# nrf24l01_r1.net
KiCad netlist of a schematic drawn in EAGLE
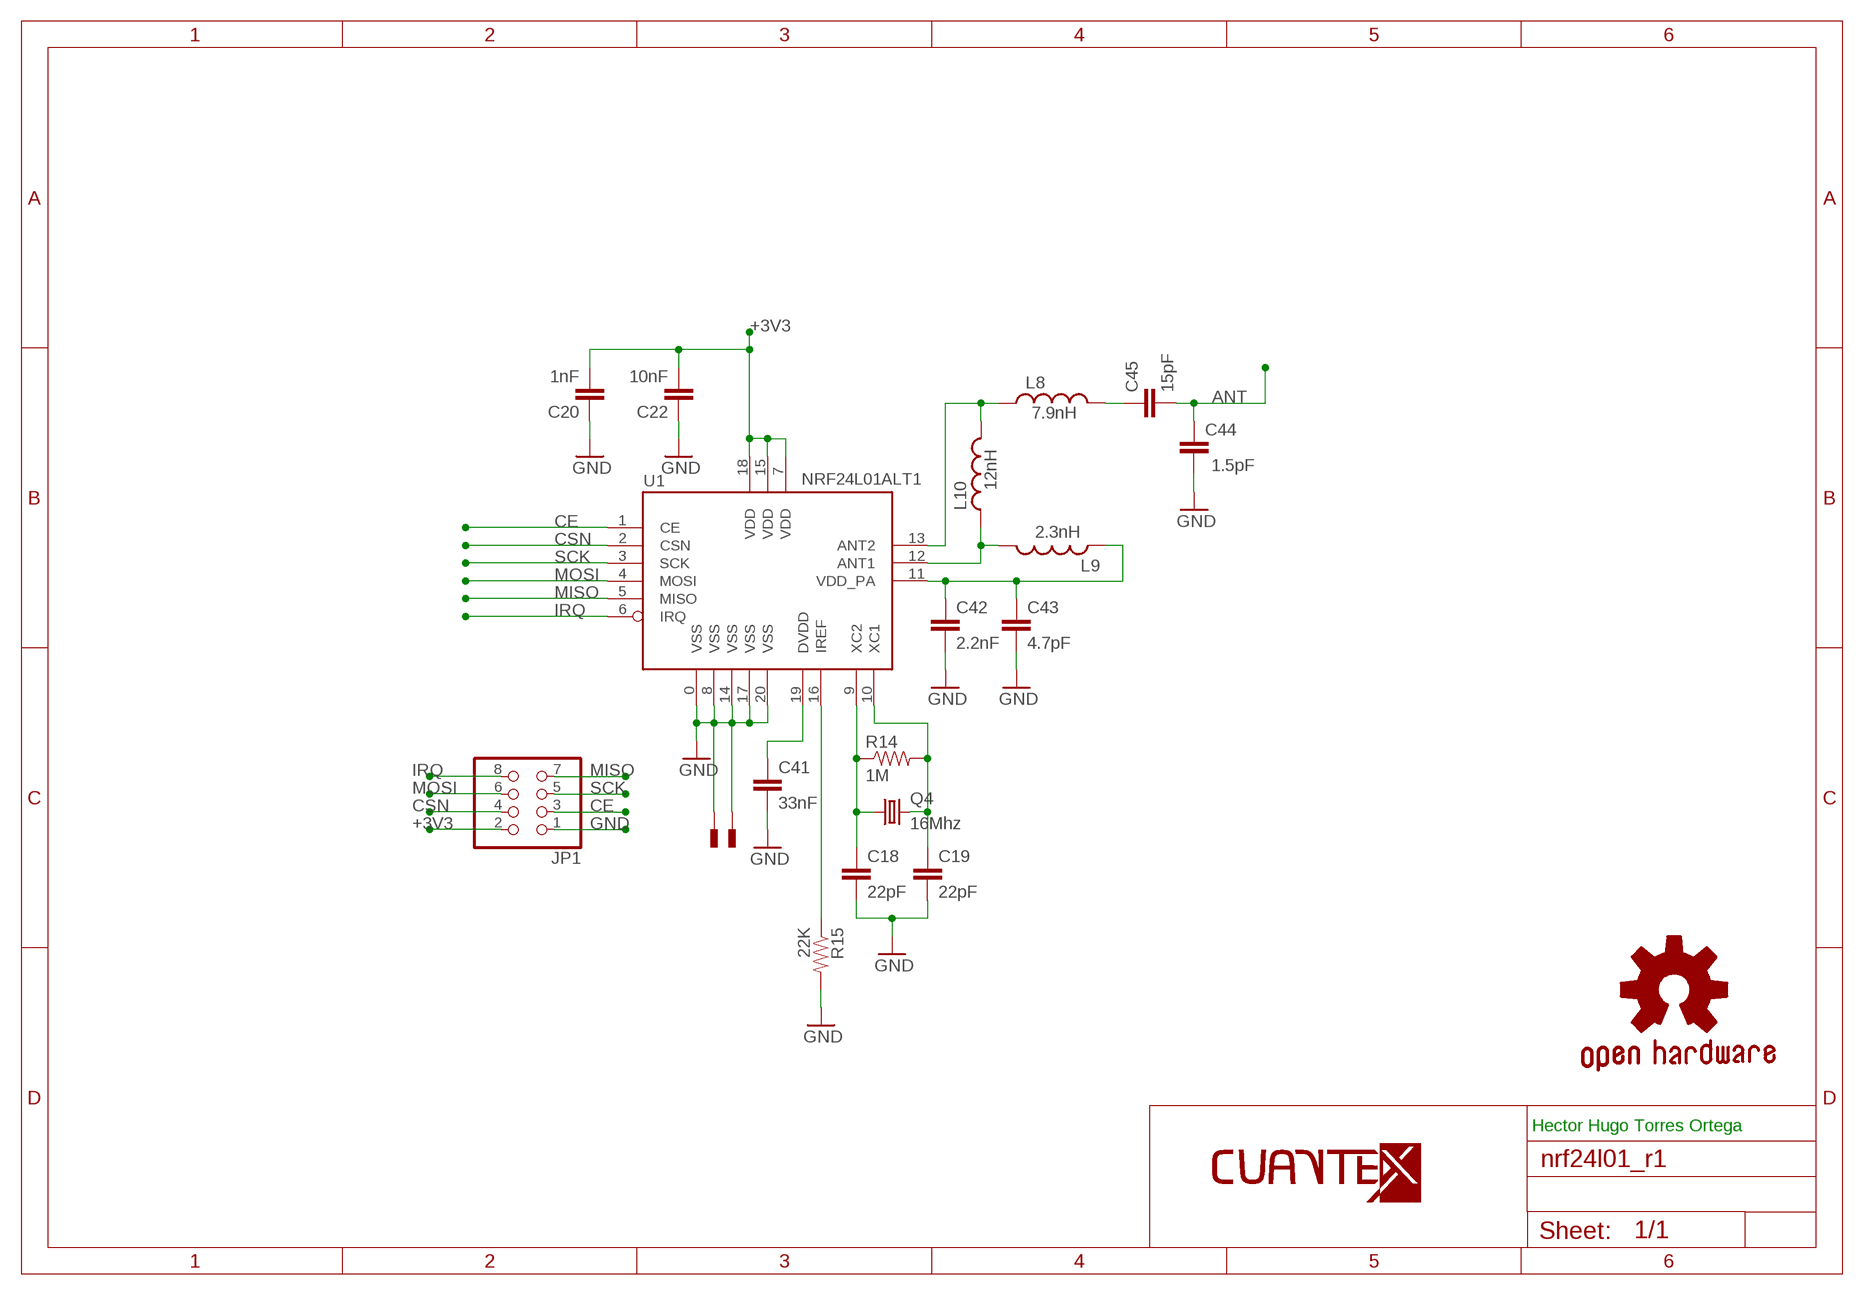
[diagram p0: schematic, sheet 1]

(export (version "E")
  (design (tool "Eeschema 10.0.6"))
  (components
    (comp (ref "C18")
      (value "22pF")
      (footprint "eagle-import:0402-CAP")
      (libsource (lib "eagle-import") (part "CAP0402-CAP"))
    )
    (comp (ref "C19")
      (value "22pF")
      (footprint "eagle-import:0402-CAP")
      (libsource (lib "eagle-import") (part "CAP0402-CAP"))
    )
    (comp (ref "C20")
      (value "1nF")
      (footprint "eagle-import:0402-CAP")
      (libsource (lib "eagle-import") (part "CAP0402-CAP"))
    )
    (comp (ref "C22")
      (value "10nF")
      (footprint "eagle-import:0402-CAP")
      (libsource (lib "eagle-import") (part "CAP0402-CAP"))
    )
    (comp (ref "C41")
      (value "33nF")
      (footprint "eagle-import:0402-CAP")
      (libsource (lib "eagle-import") (part "CAP0402-CAP"))
    )
    (comp (ref "C42")
      (value "2.2nF")
      (footprint "eagle-import:0402-CAP")
      (libsource (lib "eagle-import") (part "CAP0402-CAP"))
    )
    (comp (ref "C43")
      (value "4.7pF")
      (footprint "eagle-import:0402-CAP")
      (libsource (lib "eagle-import") (part "CAP0402-CAP"))
    )
    (comp (ref "C44")
      (value "1.5pF")
      (footprint "eagle-import:0402-CAP")
      (libsource (lib "eagle-import") (part "CAP0402-CAP"))
    )
    (comp (ref "C45")
      (value "15pF")
      (footprint "eagle-import:0402-CAP")
      (libsource (lib "eagle-import") (part "CAP0402-CAP"))
    )
    (comp (ref "GOLD_ORB_SM1")
      (value "OSHWLOGO_GOLD_ORB_SM")
      (footprint "eagle-import:OSHW2")
      (libsource (lib "eagle-import") (part "OSHWLOGO_GOLD_ORB_SM"))
    )
    (comp (ref "JP1")
      (value "PINHD-2X4")
      (footprint "eagle-import:2X04")
      (libsource (lib "eagle-import") (part "PINHD-2X4"))
    )
    (comp (ref "L8")
      (value "7.9nH")
      (footprint "eagle-import:C0402")
      (libsource (lib "eagle-import") (part "INDUCTOR0402"))
    )
    (comp (ref "L9")
      (value "2.3nH")
      (footprint "eagle-import:C0402")
      (libsource (lib "eagle-import") (part "INDUCTOR0402"))
    )
    (comp (ref "L10")
      (value "12nH")
      (footprint "eagle-import:C0402")
      (libsource (lib "eagle-import") (part "INDUCTOR0402"))
    )
    (comp (ref "Q4")
      (value "16Mhz")
      (footprint "eagle-import:HC49_S")
      (libsource (lib "eagle-import") (part "CRYSTALHC49S"))
    )
    (comp (ref "R14")
      (value "1M")
      (footprint "eagle-import:0402-RES")
      (libsource (lib "eagle-import") (part "RESISTOR0402-RES"))
    )
    (comp (ref "R15")
      (value "22K")
      (footprint "eagle-import:0402-RES")
      (libsource (lib "eagle-import") (part "RESISTOR0402-RES"))
    )
    (comp (ref "U$1")
      (value "LOGO-BOT-20MM")
      (footprint "eagle-import:B-20")
      (libsource (lib "eagle-import") (part "LOGO-BOT-20MM"))
    )
    (comp (ref "U$9")
      (value "PAD")
      (footprint "eagle-import:PAD-0.008")
      (libsource (lib "eagle-import") (part "PAD"))
    )
    (comp (ref "U$10")
      (value "PAD")
      (footprint "eagle-import:PAD-0.008")
      (libsource (lib "eagle-import") (part "PAD"))
    )
    (comp (ref "U1")
      (value "NRF24L01ALT1")
      (footprint "eagle-import:QFN20_ALT1")
      (libsource (lib "eagle-import") (part "NRF24L01ALT1"))
    )
  )
  (nets
    (net (code "1") (name "/+3V3") (class "Default")
      (node (ref "C20") (pin "2") (pinfunction "2_2") (pintype "passive"))
      (node (ref "C22") (pin "2") (pinfunction "2_2") (pintype "passive"))
      (node (ref "JP1") (pin "2") (pinfunction "2_2") (pintype "passive"))
      (node (ref "U1") (pin "15") (pinfunction "VDD_15") (pintype "power_in"))
      (node (ref "U1") (pin "18") (pinfunction "VDD_18") (pintype "power_in"))
      (node (ref "U1") (pin "7") (pinfunction "VDD_7") (pintype "power_in"))
    )
    (net (code "2") (name "/ANT") (class "Default")
      (node (ref "C44") (pin "2") (pinfunction "2_2") (pintype "passive"))
      (node (ref "C45") (pin "2") (pinfunction "2_2") (pintype "passive"))
    )
    (net (code "3") (name "/CE") (class "Default")
      (node (ref "JP1") (pin "3") (pinfunction "3_3") (pintype "passive"))
      (node (ref "U1") (pin "1") (pinfunction "CE_1") (pintype "input"))
    )
    (net (code "4") (name "/CSN") (class "Default")
      (node (ref "JP1") (pin "4") (pinfunction "4_4") (pintype "passive"))
      (node (ref "U1") (pin "2") (pinfunction "CSN_2") (pintype "input"))
    )
    (net (code "5") (name "/IRQ") (class "Default")
      (node (ref "JP1") (pin "8") (pinfunction "8_8") (pintype "passive"))
      (node (ref "U1") (pin "6") (pinfunction "IRQ_6") (pintype "output"))
    )
    (net (code "6") (name "/MISO") (class "Default")
      (node (ref "JP1") (pin "7") (pinfunction "7_7") (pintype "passive"))
      (node (ref "U1") (pin "5") (pinfunction "MISO_5") (pintype "output"))
    )
    (net (code "7") (name "/MOSI") (class "Default")
      (node (ref "JP1") (pin "6") (pinfunction "6_6") (pintype "passive"))
      (node (ref "U1") (pin "4") (pinfunction "MOSI_4") (pintype "input"))
    )
    (net (code "8") (name "/SCK") (class "Default")
      (node (ref "JP1") (pin "5") (pinfunction "5_5") (pintype "passive"))
      (node (ref "U1") (pin "3") (pinfunction "SCK_3") (pintype "input"))
    )
    (net (code "9") (name "GND") (class "Default")
      (node (ref "C18") (pin "2") (pinfunction "2_2") (pintype "passive"))
      (node (ref "C19") (pin "2") (pinfunction "2_2") (pintype "passive"))
      (node (ref "C20") (pin "1") (pinfunction "1_1") (pintype "passive"))
      (node (ref "C22") (pin "1") (pinfunction "1_1") (pintype "passive"))
      (node (ref "C41") (pin "2") (pinfunction "2_2") (pintype "passive"))
      (node (ref "C42") (pin "2") (pinfunction "2_2") (pintype "passive"))
      (node (ref "C43") (pin "2") (pinfunction "2_2") (pintype "passive"))
      (node (ref "C44") (pin "1") (pinfunction "1_1") (pintype "passive"))
      (node (ref "JP1") (pin "1") (pinfunction "1_1") (pintype "passive"))
      (node (ref "R15") (pin "2") (pinfunction "2_2") (pintype "passive"))
      (node (ref "U$10") (pin "P$1") (pinfunction "P$1_P$1") (pintype "bidirectional"))
      (node (ref "U$9") (pin "P$1") (pinfunction "P$1_P$1") (pintype "bidirectional"))
      (node (ref "U1") (pin "0") (pinfunction "VSS_0") (pintype "power_in"))
      (node (ref "U1") (pin "14") (pinfunction "VSS_14") (pintype "power_in"))
      (node (ref "U1") (pin "17") (pinfunction "VSS_17") (pintype "power_in"))
      (node (ref "U1") (pin "20") (pinfunction "VSS_20") (pintype "power_in"))
      (node (ref "U1") (pin "8") (pinfunction "VSS_8") (pintype "power_in"))
    )
    (net (code "10") (name "Net-(C45-Pad1)") (class "Default")
      (node (ref "C45") (pin "1") (pinfunction "1_1") (pintype "passive"))
      (node (ref "L8") (pin "2") (pinfunction "2_2") (pintype "passive"))
    )
    (net (code "11") (name "Net-(U1-ANT1)") (class "Default")
      (node (ref "L10") (pin "1") (pinfunction "1_1") (pintype "passive"))
      (node (ref "L9") (pin "2") (pinfunction "2_2") (pintype "passive"))
      (node (ref "U1") (pin "12") (pinfunction "ANT1_12") (pintype "output"))
    )
    (net (code "12") (name "Net-(U1-ANT2)") (class "Default")
      (node (ref "L10") (pin "2") (pinfunction "2_2") (pintype "passive"))
      (node (ref "L8") (pin "1") (pinfunction "1_1") (pintype "passive"))
      (node (ref "U1") (pin "13") (pinfunction "ANT2_13") (pintype "output"))
    )
    (net (code "13") (name "Net-(U1-DVDD)") (class "Default")
      (node (ref "C41") (pin "1") (pinfunction "1_1") (pintype "passive"))
      (node (ref "U1") (pin "19") (pinfunction "DVDD_19") (pintype "power_in"))
    )
    (net (code "14") (name "Net-(U1-IREF)") (class "Default")
      (node (ref "R15") (pin "1") (pinfunction "1_1") (pintype "passive"))
      (node (ref "U1") (pin "16") (pinfunction "IREF_16") (pintype "input"))
    )
    (net (code "15") (name "Net-(U1-VDD_PA)") (class "Default")
      (node (ref "C42") (pin "1") (pinfunction "1_1") (pintype "passive"))
      (node (ref "C43") (pin "1") (pinfunction "1_1") (pintype "passive"))
      (node (ref "L9") (pin "1") (pinfunction "1_1") (pintype "passive"))
      (node (ref "U1") (pin "11") (pinfunction "VDD_PA_11") (pintype "power_in"))
    )
    (net (code "16") (name "Net-(U1-XC1)") (class "Default")
      (node (ref "C19") (pin "1") (pinfunction "1_1") (pintype "passive"))
      (node (ref "Q4") (pin "2") (pinfunction "2_2") (pintype "passive"))
      (node (ref "R14") (pin "2") (pinfunction "2_2") (pintype "passive"))
      (node (ref "U1") (pin "10") (pinfunction "XC1_10") (pintype "input"))
    )
    (net (code "17") (name "Net-(U1-XC2)") (class "Default")
      (node (ref "C18") (pin "1") (pinfunction "1_1") (pintype "passive"))
      (node (ref "Q4") (pin "1") (pinfunction "1_1") (pintype "passive"))
      (node (ref "R14") (pin "1") (pinfunction "1_1") (pintype "passive"))
      (node (ref "U1") (pin "9") (pinfunction "XC2_9") (pintype "input"))
    )
  )
)
